# schematic.net
KiCad netlist of a schematic drawn in EAGLE
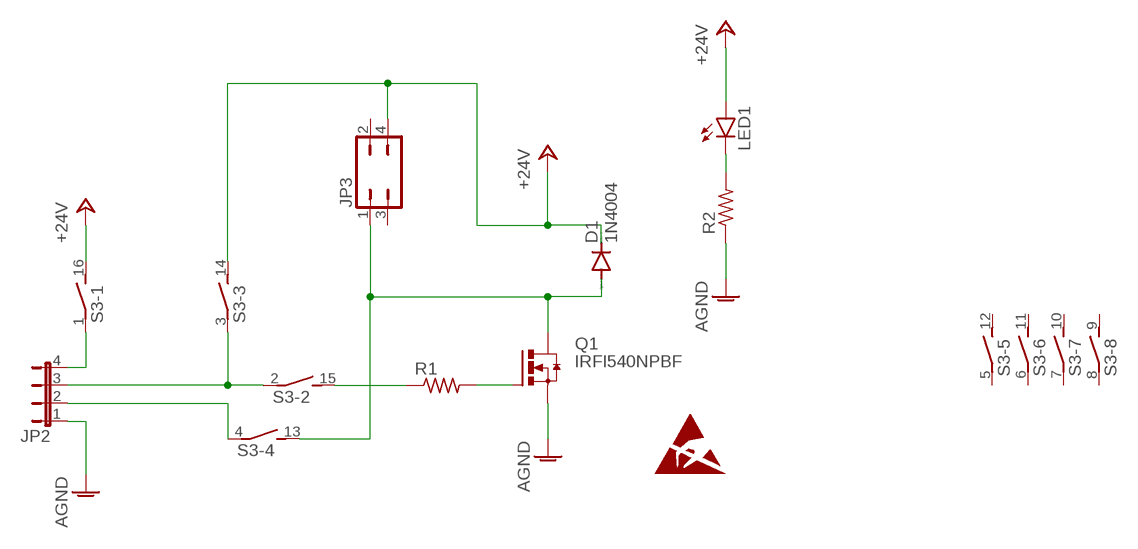
[diagram p0: schematic, sheet 1]

(export (version "E")
  (design (tool "Eeschema 10.0.6"))
  (components
    (comp (ref "D1")
      (value "1N4004")
      (footprint "eagle-import:DO41-10")
      (libsource (lib "eagle-import") (part "1N4004"))
    )
    (comp (ref "JP2")
      (value "JP4E")
      (footprint "eagle-import:JP4")
      (libsource (lib "eagle-import") (part "JP4E"))
    )
    (comp (ref "JP3")
      (value "JP2Q")
      (footprint "eagle-import:JP2Q")
      (libsource (lib "eagle-import") (part "JP2Q"))
    )
    (comp (ref "LED1")
      (value "LED3MM")
      (footprint "eagle-import:LED3MM")
      (libsource (lib "eagle-import") (part "LED3MM"))
    )
    (comp (ref "Q1")
      (value "IRFI540NPBF")
      (footprint "eagle-import:TO220BH")
      (libsource (lib "eagle-import") (part "IRFI540NPBF"))
    )
    (comp (ref "R1")
      (value "R-US_M0805")
      (footprint "eagle-import:M0805")
      (libsource (lib "eagle-import") (part "R-US_M0805"))
    )
    (comp (ref "R2")
      (value "R-US_0411/15")
      (footprint "eagle-import:0411_15")
      (libsource (lib "eagle-import") (part "R-US_0411/15"))
    )
    (comp (ref "S3")
      (value "DIP08S")
      (footprint "eagle-import:DIP08S")
      (libsource (lib "eagle-import") (part "DIP08S"))
    )
  )
  (nets
    (net (code "1") (name "+24V") (class "Default")
      (node (ref "D1") (pin "C") (pinfunction "C_C") (pintype "passive"))
      (node (ref "JP3") (pin "4") (pinfunction "4_4") (pintype "passive"))
      (node (ref "LED1") (pin "A") (pinfunction "A_A") (pintype "passive"))
      (node (ref "S3") (pin "14") (pinfunction "2_14") (pintype "passive"))
      (node (ref "S3") (pin "16") (pinfunction "2_16") (pintype "passive"))
    )
    (net (code "2") (name "AGND") (class "Default")
      (node (ref "JP2") (pin "1") (pinfunction "1_1") (pintype "passive"))
      (node (ref "Q1") (pin "S") (pinfunction "S_S") (pintype "passive"))
      (node (ref "R2") (pin "1") (pinfunction "1_1") (pintype "passive"))
    )
    (net (code "3") (name "Net-(JP2-Pad4)") (class "Default")
      (node (ref "JP2") (pin "4") (pinfunction "4_4") (pintype "passive"))
      (node (ref "S3") (pin "1") (pinfunction "1_1") (pintype "passive"))
    )
    (net (code "4") (name "Net-(LED1-C)") (class "Default")
      (node (ref "LED1") (pin "K") (pinfunction "C_K") (pintype "passive"))
      (node (ref "R2") (pin "2") (pinfunction "2_2") (pintype "passive"))
    )
    (net (code "5") (name "Net-(Q1-PadG)") (class "Default")
      (node (ref "Q1") (pin "G") (pinfunction "G_G") (pintype "passive"))
      (node (ref "R1") (pin "2") (pinfunction "2_2") (pintype "passive"))
    )
    (net (code "6") (name "Net-(S3B-1)") (class "Default")
      (node (ref "JP2") (pin "3") (pinfunction "3_3") (pintype "passive"))
      (node (ref "S3") (pin "2") (pinfunction "1_2") (pintype "passive"))
      (node (ref "S3") (pin "3") (pinfunction "1_3") (pintype "passive"))
    )
    (net (code "7") (name "Net-(S3B-2)") (class "Default")
      (node (ref "R1") (pin "1") (pinfunction "1_1") (pintype "passive"))
      (node (ref "S3") (pin "15") (pinfunction "2_15") (pintype "passive"))
    )
    (net (code "8") (name "Net-(S3D-1)") (class "Default")
      (node (ref "JP2") (pin "2") (pinfunction "2_2") (pintype "passive"))
      (node (ref "S3") (pin "4") (pinfunction "1_4") (pintype "passive"))
    )
    (net (code "9") (name "Net-(S3D-2)") (class "Default")
      (node (ref "D1") (pin "A") (pinfunction "A_A") (pintype "passive"))
      (node (ref "JP3") (pin "1") (pinfunction "1_1") (pintype "passive"))
      (node (ref "Q1") (pin "D") (pinfunction "D_D") (pintype "passive"))
      (node (ref "S3") (pin "13") (pinfunction "2_13") (pintype "passive"))
    )
    (net (code "10") (name "unconnected-(JP3-Pad2)") (class "Default")
      (node (ref "JP3") (pin "2") (pinfunction "2_2") (pintype "passive"))
    )
    (net (code "11") (name "unconnected-(JP3-Pad3)") (class "Default")
      (node (ref "JP3") (pin "3") (pinfunction "3_3") (pintype "passive"))
    )
    (net (code "12") (name "unconnected-(S3E-1-Pad5)") (class "Default")
      (node (ref "S3") (pin "5") (pinfunction "1_5") (pintype "passive"))
    )
    (net (code "13") (name "unconnected-(S3E-2-Pad12)") (class "Default")
      (node (ref "S3") (pin "12") (pinfunction "2_12") (pintype "passive"))
    )
    (net (code "14") (name "unconnected-(S3F-1-Pad6)") (class "Default")
      (node (ref "S3") (pin "6") (pinfunction "1_6") (pintype "passive"))
    )
    (net (code "15") (name "unconnected-(S3F-2-Pad11)") (class "Default")
      (node (ref "S3") (pin "11") (pinfunction "2_11") (pintype "passive"))
    )
    (net (code "16") (name "unconnected-(S3G-1-Pad7)") (class "Default")
      (node (ref "S3") (pin "7") (pinfunction "1_7") (pintype "passive"))
    )
    (net (code "17") (name "unconnected-(S3G-2-Pad10)") (class "Default")
      (node (ref "S3") (pin "10") (pinfunction "2_10") (pintype "passive"))
    )
    (net (code "18") (name "unconnected-(S3H-1-Pad8)") (class "Default")
      (node (ref "S3") (pin "8") (pinfunction "1_8") (pintype "passive"))
    )
    (net (code "19") (name "unconnected-(S3H-2-Pad9)") (class "Default")
      (node (ref "S3") (pin "9") (pinfunction "2_9") (pintype "passive"))
    )
  )
)
